# SCH.net
KiCad netlist of a schematic drawn in EasyEDA Pro
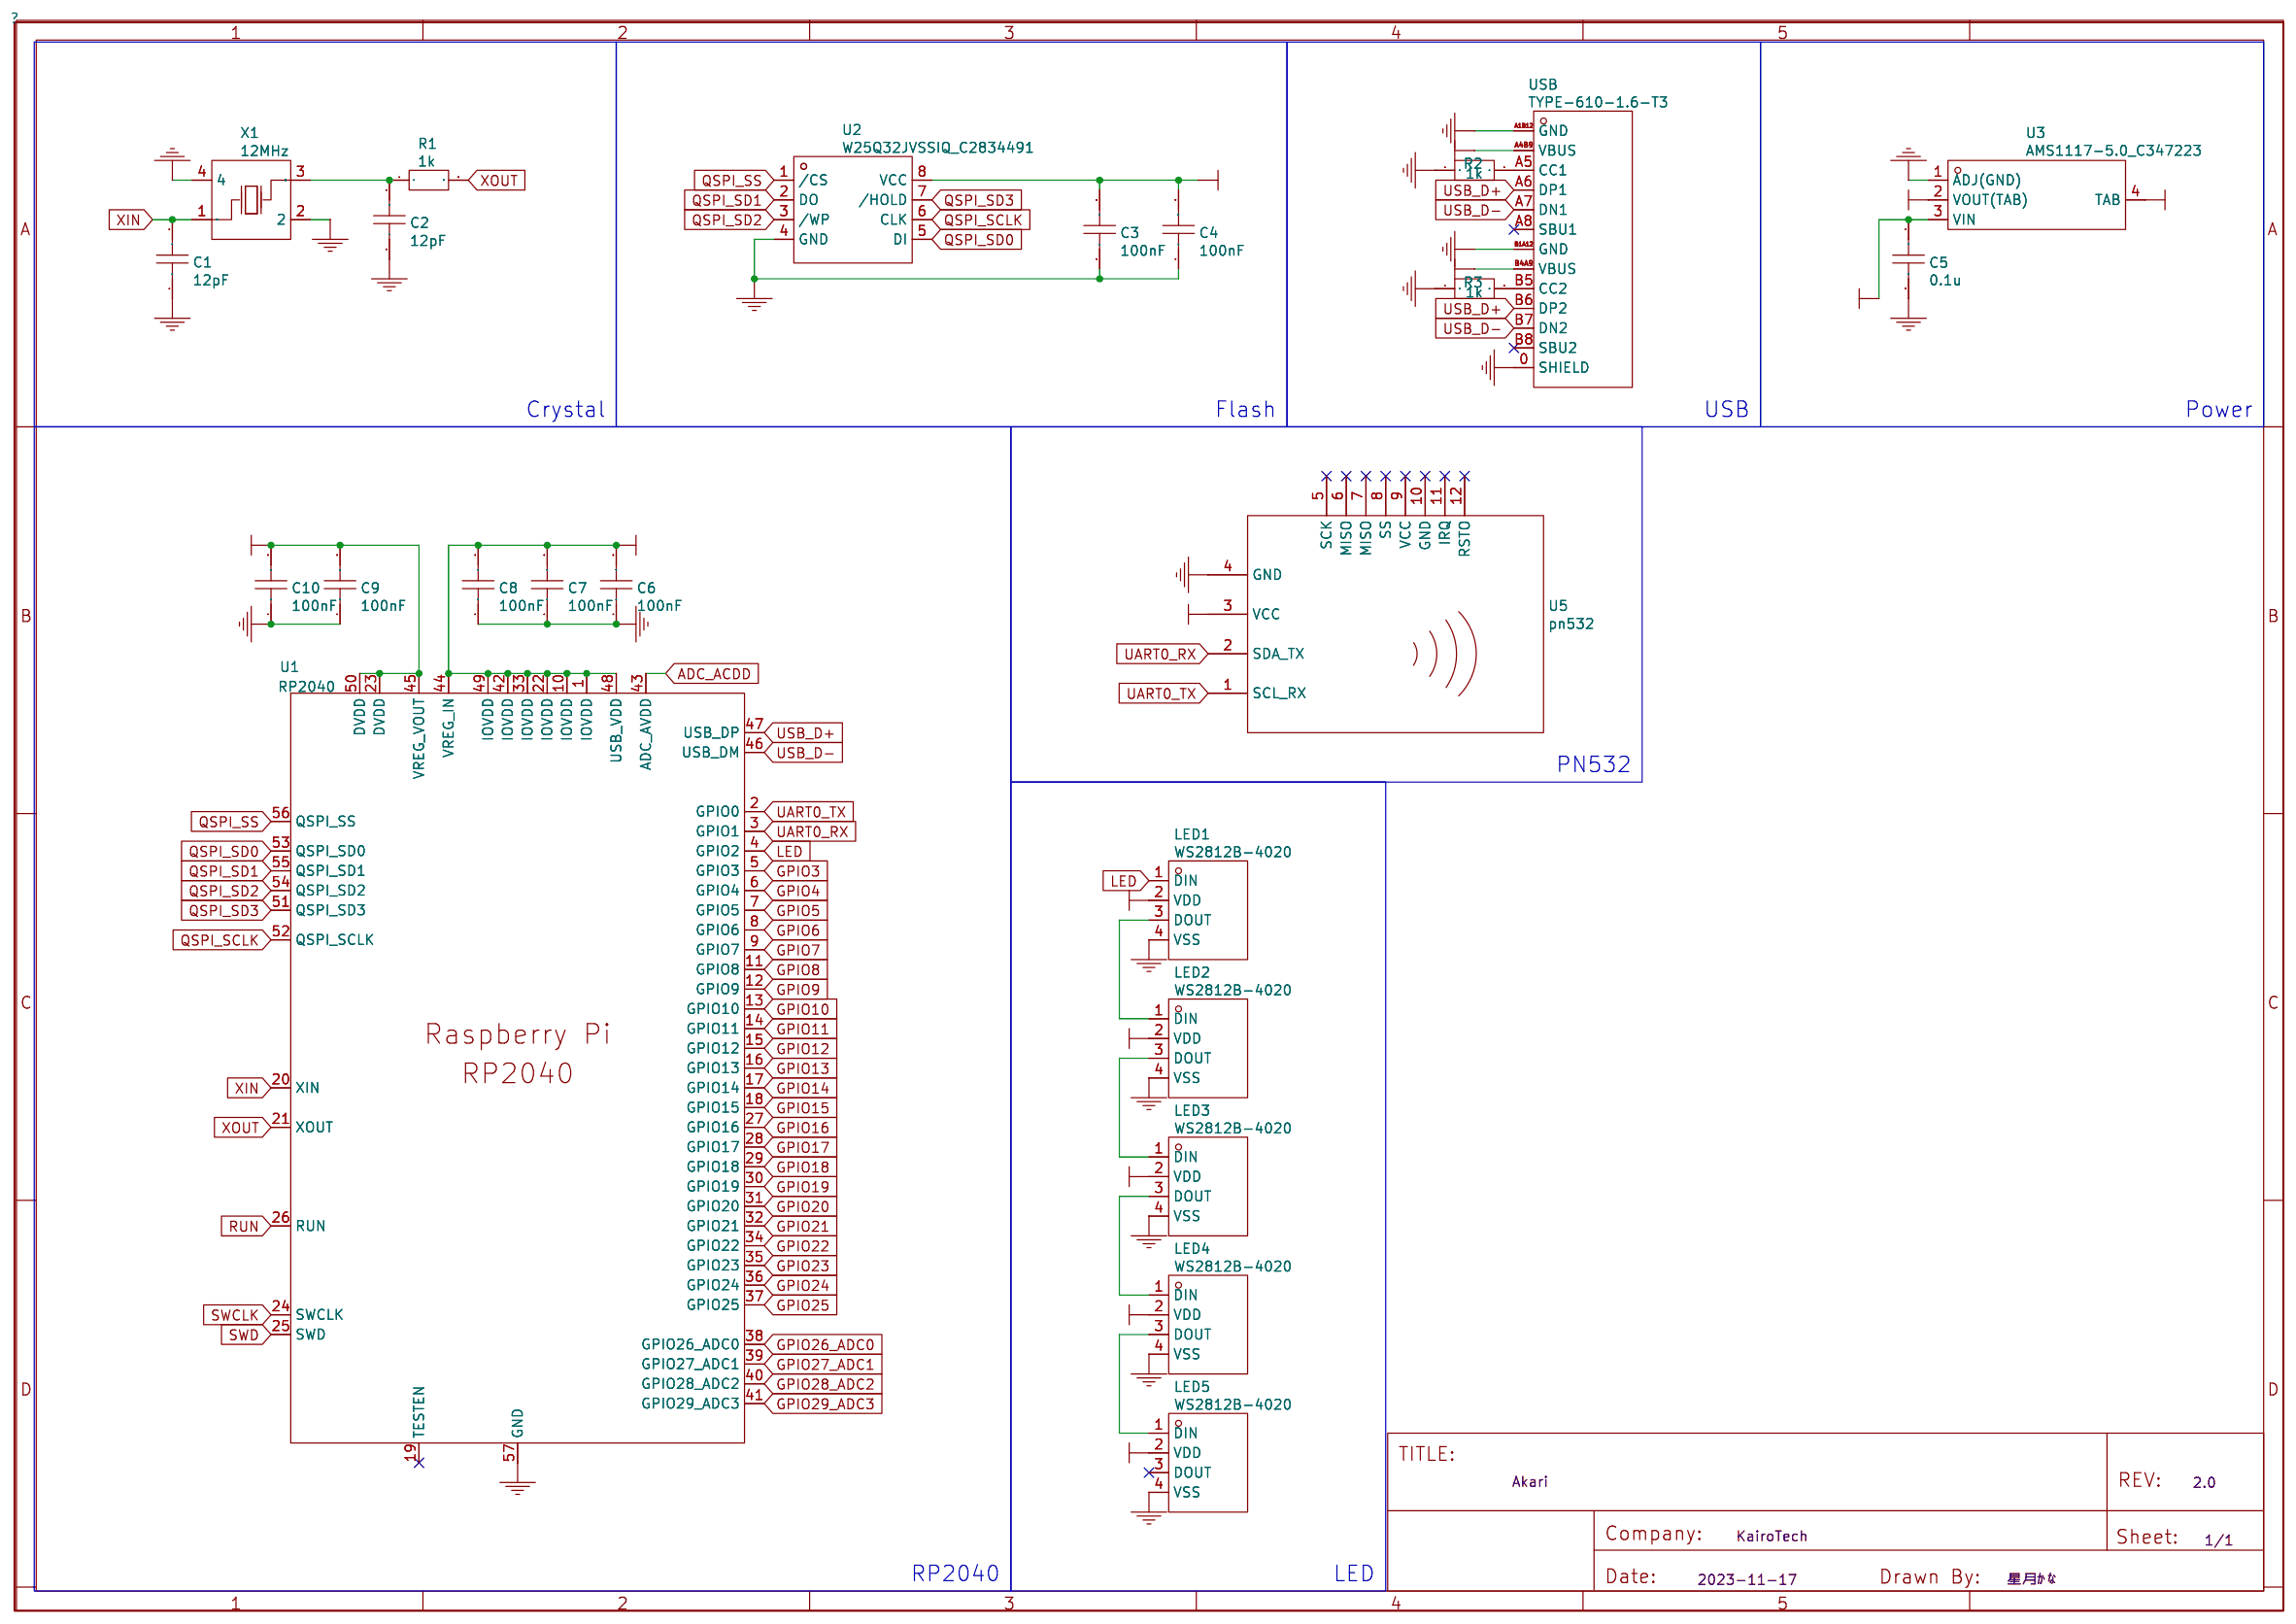
[diagram p0: schematic sheet]

(export (version "E")
  (design (tool "Eeschema 10.0.6"))
  (components
    (comp (ref "C1")
      (value "12pF")
      (footprint "easyedapro:C0603")
      (libsource (lib "easyedapro") (part "12pF"))
    )
    (comp (ref "C2")
      (value "12pF")
      (footprint "easyedapro:C0603")
      (libsource (lib "easyedapro") (part "12pF"))
    )
    (comp (ref "C3")
      (value "100nF")
      (footprint "easyedapro:C0603")
      (libsource (lib "easyedapro") (part "100nF"))
    )
    (comp (ref "C4")
      (value "100nF")
      (footprint "easyedapro:C0603")
      (libsource (lib "easyedapro") (part "100nF"))
    )
    (comp (ref "C5")
      (value "0.1u")
      (footprint "easyedapro:C0603")
      (libsource (lib "easyedapro") (part "0.1u"))
    )
    (comp (ref "C6")
      (value "100nF")
      (footprint "easyedapro:C0603")
      (libsource (lib "easyedapro") (part "100nF"))
    )
    (comp (ref "C7")
      (value "100nF")
      (footprint "easyedapro:C0603")
      (libsource (lib "easyedapro") (part "100nF"))
    )
    (comp (ref "C8")
      (value "100nF")
      (footprint "easyedapro:C0603")
      (libsource (lib "easyedapro") (part "100nF"))
    )
    (comp (ref "C9")
      (value "100nF")
      (footprint "easyedapro:C0603")
      (libsource (lib "easyedapro") (part "100nF"))
    )
    (comp (ref "C10")
      (value "100nF")
      (footprint "easyedapro:C0603")
      (libsource (lib "easyedapro") (part "100nF"))
    )
    (comp (ref "LED1")
      (value "WS2812B-4020")
      (footprint "easyedapro:LED-SMD_WS2812B-4020")
      (fields (field (name "Manufacturer") "worldsemi"))
      (libsource (lib "easyedapro") (part "WS2812B-4020"))
    )
    (comp (ref "LED2")
      (value "WS2812B-4020")
      (footprint "easyedapro:LED-SMD_WS2812B-4020")
      (fields (field (name "Manufacturer") "worldsemi"))
      (libsource (lib "easyedapro") (part "WS2812B-4020"))
    )
    (comp (ref "LED3")
      (value "WS2812B-4020")
      (footprint "easyedapro:LED-SMD_WS2812B-4020")
      (fields (field (name "Manufacturer") "worldsemi"))
      (libsource (lib "easyedapro") (part "WS2812B-4020"))
    )
    (comp (ref "LED4")
      (value "WS2812B-4020")
      (footprint "easyedapro:LED-SMD_WS2812B-4020")
      (fields (field (name "Manufacturer") "worldsemi"))
      (libsource (lib "easyedapro") (part "WS2812B-4020"))
    )
    (comp (ref "LED5")
      (value "WS2812B-4020")
      (footprint "easyedapro:LED-SMD_WS2812B-4020")
      (fields (field (name "Manufacturer") "worldsemi"))
      (libsource (lib "easyedapro") (part "WS2812B-4020"))
    )
    (comp (ref "R1") (value "1k") (footprint "easyedapro:R0603") (libsource (lib "easyedapro") (part "1k")))
    (comp (ref "R2") (value "1k") (footprint "easyedapro:R0603") (libsource (lib "easyedapro") (part "1k")))
    (comp (ref "R3") (value "1k") (footprint "easyedapro:R0603") (libsource (lib "easyedapro") (part "1k")))
    (comp (ref "U1")
      (value "RP2040")
      (footprint "easyedapro:LQFN-56_L7.0-W7.0-P0.4-EP")
      (fields (field (name "Manufacturer") "Raspberry Pi(树莓派)"))
      (libsource (lib "easyedapro") (part "RP2040"))
    )
    (comp (ref "U2")
      (value "W25Q32JVSSIQ_C2834491")
      (footprint "easyedapro:SOIC-8_L5.2-W5.2-P1.27-LS7.9-BL")
      (fields (field (name "Manufacturer Part") "W25Q32JVSSIQ") (field (name "Manufacturer") "WINBOND(华邦)"))
      (libsource (lib "easyedapro") (part "W25Q32JVSSIQ_C2834491"))
    )
    (comp (ref "U3")
      (value "AMS1117-5.0_C347223")
      (footprint "easyedapro:SOT-223_L6.7-W3.5-P2.30-BR")
      (fields (field (name "Manufacturer Part") "AMS1117-5.0") (field (name "Manufacturer") "UMW(广东友台半导体)"))
      (libsource (lib "easyedapro") (part "AMS1117-5.0_C347223"))
    )
    (comp (ref "U5")
      (value "pn532")
      (footprint "easyedapro:PN532")
      (libsource (lib "easyedapro") (part "pn532"))
    )
    (comp (ref "USB")
      (value "TYPE-610-1.6-T3")
      (footprint "easyedapro:USB-C-SMD_TYPE-C-16P-610-1.6-T3")
      (fields (field (name "Manufacturer") "Yuandi(元迪)"))
      (libsource (lib "easyedapro") (part "TYPE-610-1.6-T3"))
    )
    (comp (ref "X1")
      (value "12MHz")
      (footprint "easyedapro:CRYSTAL-SMD_4P-L2.5-W2.0-BL_XTAL12MHZ")
      (fields
        (field (name "Manufacturer Part") "ABM10AIG-12.000MHZ-4Z-T3")
        (field (name "Manufacturer") "ABRACON")
      )
      (libsource (lib "easyedapro") (part "12MHz"))
    )
  )
  (nets
    (net (code "1") (name "1V1") (class "Default")
      (node (ref "C10") (pin "2") (pinfunction "2_2") (pintype "unspecified"))
      (node (ref "C9") (pin "2") (pinfunction "2_2") (pintype "unspecified"))
      (node (ref "U1") (pin "23") (pinfunction "DVDD_23") (pintype "bidirectional"))
      (node (ref "U1") (pin "45") (pinfunction "VREG_VOUT_45") (pintype "bidirectional"))
      (node (ref "U1") (pin "50") (pinfunction "DVDD_50") (pintype "bidirectional"))
    )
    (net (code "2") (name "3V3") (class "Default")
      (node (ref "C3") (pin "2") (pinfunction "2_2") (pintype "unspecified"))
      (node (ref "C4") (pin "2") (pinfunction "2_2") (pintype "unspecified"))
      (node (ref "C6") (pin "2") (pinfunction "2_2") (pintype "unspecified"))
      (node (ref "C7") (pin "2") (pinfunction "2_2") (pintype "unspecified"))
      (node (ref "C8") (pin "2") (pinfunction "2_2") (pintype "unspecified"))
      (node (ref "U1") (pin "1") (pinfunction "IOVDD_1") (pintype "bidirectional"))
      (node (ref "U1") (pin "10") (pinfunction "IOVDD_10") (pintype "bidirectional"))
      (node (ref "U1") (pin "22") (pinfunction "IOVDD_22") (pintype "bidirectional"))
      (node (ref "U1") (pin "33") (pinfunction "IOVDD_33") (pintype "bidirectional"))
      (node (ref "U1") (pin "42") (pinfunction "IOVDD_42") (pintype "bidirectional"))
      (node (ref "U1") (pin "44") (pinfunction "VREG_IN_44") (pintype "bidirectional"))
      (node (ref "U1") (pin "48") (pinfunction "USB_VDD_48") (pintype "bidirectional"))
      (node (ref "U1") (pin "49") (pinfunction "IOVDD_49") (pintype "bidirectional"))
      (node (ref "U2") (pin "8") (pinfunction "VCC_8") (pintype "unspecified"))
      (node (ref "U3") (pin "2") (pinfunction "VOUT(TAB)_2") (pintype "unspecified"))
      (node (ref "U3") (pin "4") (pinfunction "TAB_4") (pintype "unspecified"))
    )
    (net (code "3") (name "ADC_ACDD") (class "Default")
      (node (ref "U1") (pin "43") (pinfunction "ADC_AVDD_43") (pintype "bidirectional"))
    )
    (net (code "4") (name "GND") (class "Default")
      (node (ref "C1") (pin "1") (pinfunction "1_1") (pintype "unspecified"))
      (node (ref "C10") (pin "1") (pinfunction "1_1") (pintype "unspecified"))
      (node (ref "C2") (pin "2") (pinfunction "2_2") (pintype "unspecified"))
      (node (ref "C3") (pin "1") (pinfunction "1_1") (pintype "unspecified"))
      (node (ref "C4") (pin "1") (pinfunction "1_1") (pintype "unspecified"))
      (node (ref "C5") (pin "2") (pinfunction "2_2") (pintype "unspecified"))
      (node (ref "C6") (pin "1") (pinfunction "1_1") (pintype "unspecified"))
      (node (ref "C7") (pin "1") (pinfunction "1_1") (pintype "unspecified"))
      (node (ref "C8") (pin "1") (pinfunction "1_1") (pintype "unspecified"))
      (node (ref "C9") (pin "1") (pinfunction "1_1") (pintype "unspecified"))
      (node (ref "LED1") (pin "4") (pinfunction "VSS_4") (pintype "unspecified"))
      (node (ref "LED2") (pin "4") (pinfunction "VSS_4") (pintype "unspecified"))
      (node (ref "LED3") (pin "4") (pinfunction "VSS_4") (pintype "unspecified"))
      (node (ref "LED4") (pin "4") (pinfunction "VSS_4") (pintype "unspecified"))
      (node (ref "LED5") (pin "4") (pinfunction "VSS_4") (pintype "unspecified"))
      (node (ref "R2") (pin "1") (pinfunction "1_1") (pintype "unspecified"))
      (node (ref "R3") (pin "1") (pinfunction "1_1") (pintype "unspecified"))
      (node (ref "U1") (pin "57") (pinfunction "GND_57") (pintype "bidirectional"))
      (node (ref "U2") (pin "4") (pinfunction "GND_4") (pintype "unspecified"))
      (node (ref "U3") (pin "1") (pinfunction "ADJ(GND)_1") (pintype "unspecified"))
      (node (ref "U5") (pin "4") (pinfunction "GND_4") (pintype "unspecified"))
      (node (ref "USB") (pin "0") (pinfunction "SHIELD_0") (pintype "unspecified"))
      (node (ref "USB") (pin "A1B12") (pinfunction "GND_A1B12") (pintype "unspecified"))
      (node (ref "USB") (pin "B1A12") (pinfunction "GND_B1A12") (pintype "unspecified"))
      (node (ref "X1") (pin "2") (pinfunction "2_2") (pintype "unspecified"))
      (node (ref "X1") (pin "4") (pinfunction "4_4") (pintype "unspecified"))
    )
    (net (code "5") (name "GPIO3") (class "Default")
      (node (ref "U1") (pin "5") (pinfunction "GPIO3_5") (pintype "bidirectional"))
    )
    (net (code "6") (name "GPIO4") (class "Default")
      (node (ref "U1") (pin "6") (pinfunction "GPIO4_6") (pintype "bidirectional"))
    )
    (net (code "7") (name "GPIO5") (class "Default")
      (node (ref "U1") (pin "7") (pinfunction "GPIO5_7") (pintype "bidirectional"))
    )
    (net (code "8") (name "GPIO6") (class "Default")
      (node (ref "U1") (pin "8") (pinfunction "GPIO6_8") (pintype "bidirectional"))
    )
    (net (code "9") (name "GPIO7") (class "Default")
      (node (ref "U1") (pin "9") (pinfunction "GPIO7_9") (pintype "bidirectional"))
    )
    (net (code "10") (name "GPIO8") (class "Default")
      (node (ref "U1") (pin "11") (pinfunction "GPIO8_11") (pintype "bidirectional"))
    )
    (net (code "11") (name "GPIO9") (class "Default")
      (node (ref "U1") (pin "12") (pinfunction "GPIO9_12") (pintype "bidirectional"))
    )
    (net (code "12") (name "GPIO10") (class "Default")
      (node (ref "U1") (pin "13") (pinfunction "GPIO10_13") (pintype "bidirectional"))
    )
    (net (code "13") (name "GPIO11") (class "Default")
      (node (ref "U1") (pin "14") (pinfunction "GPIO11_14") (pintype "bidirectional"))
    )
    (net (code "14") (name "GPIO12") (class "Default")
      (node (ref "U1") (pin "15") (pinfunction "GPIO12_15") (pintype "bidirectional"))
    )
    (net (code "15") (name "GPIO13") (class "Default")
      (node (ref "U1") (pin "16") (pinfunction "GPIO13_16") (pintype "bidirectional"))
    )
    (net (code "16") (name "GPIO14") (class "Default")
      (node (ref "U1") (pin "17") (pinfunction "GPIO14_17") (pintype "bidirectional"))
    )
    (net (code "17") (name "GPIO15") (class "Default")
      (node (ref "U1") (pin "18") (pinfunction "GPIO15_18") (pintype "bidirectional"))
    )
    (net (code "18") (name "GPIO16") (class "Default")
      (node (ref "U1") (pin "27") (pinfunction "GPIO16_27") (pintype "bidirectional"))
    )
    (net (code "19") (name "GPIO17") (class "Default")
      (node (ref "U1") (pin "28") (pinfunction "GPIO17_28") (pintype "bidirectional"))
    )
    (net (code "20") (name "GPIO18") (class "Default")
      (node (ref "U1") (pin "29") (pinfunction "GPIO18_29") (pintype "bidirectional"))
    )
    (net (code "21") (name "GPIO19") (class "Default")
      (node (ref "U1") (pin "30") (pinfunction "GPIO19_30") (pintype "bidirectional"))
    )
    (net (code "22") (name "GPIO20") (class "Default")
      (node (ref "U1") (pin "31") (pinfunction "GPIO20_31") (pintype "bidirectional"))
    )
    (net (code "23") (name "GPIO21") (class "Default")
      (node (ref "U1") (pin "32") (pinfunction "GPIO21_32") (pintype "bidirectional"))
    )
    (net (code "24") (name "GPIO22") (class "Default")
      (node (ref "U1") (pin "34") (pinfunction "GPIO22_34") (pintype "bidirectional"))
    )
    (net (code "25") (name "GPIO23") (class "Default")
      (node (ref "U1") (pin "35") (pinfunction "GPIO23_35") (pintype "bidirectional"))
    )
    (net (code "26") (name "GPIO24") (class "Default")
      (node (ref "U1") (pin "36") (pinfunction "GPIO24_36") (pintype "bidirectional"))
    )
    (net (code "27") (name "GPIO25") (class "Default")
      (node (ref "U1") (pin "37") (pinfunction "GPIO25_37") (pintype "bidirectional"))
    )
    (net (code "28") (name "GPIO26_ADC0") (class "Default")
      (node (ref "U1") (pin "38") (pinfunction "GPIO26_ADC0_38") (pintype "bidirectional"))
    )
    (net (code "29") (name "GPIO27_ADC1") (class "Default")
      (node (ref "U1") (pin "39") (pinfunction "GPIO27_ADC1_39") (pintype "bidirectional"))
    )
    (net (code "30") (name "GPIO28_ADC2") (class "Default")
      (node (ref "U1") (pin "40") (pinfunction "GPIO28_ADC2_40") (pintype "bidirectional"))
    )
    (net (code "31") (name "GPIO29_ADC3") (class "Default")
      (node (ref "U1") (pin "41") (pinfunction "GPIO29_ADC3_41") (pintype "bidirectional"))
    )
    (net (code "32") (name "LED") (class "Default")
      (node (ref "LED1") (pin "1") (pinfunction "DIN_1") (pintype "unspecified"))
      (node (ref "U1") (pin "4") (pinfunction "GPIO2_4") (pintype "bidirectional"))
    )
    (net (code "33") (name "Net-(LED1-DOUT)") (class "Default")
      (node (ref "LED1") (pin "3") (pinfunction "DOUT_3") (pintype "unspecified"))
      (node (ref "LED2") (pin "1") (pinfunction "DIN_1") (pintype "unspecified"))
    )
    (net (code "34") (name "Net-(LED2-DOUT)") (class "Default")
      (node (ref "LED2") (pin "3") (pinfunction "DOUT_3") (pintype "unspecified"))
      (node (ref "LED3") (pin "1") (pinfunction "DIN_1") (pintype "unspecified"))
    )
    (net (code "35") (name "Net-(LED3-DOUT)") (class "Default")
      (node (ref "LED3") (pin "3") (pinfunction "DOUT_3") (pintype "unspecified"))
      (node (ref "LED4") (pin "1") (pinfunction "DIN_1") (pintype "unspecified"))
    )
    (net (code "36") (name "Net-(LED4-DOUT)") (class "Default")
      (node (ref "LED4") (pin "3") (pinfunction "DOUT_3") (pintype "unspecified"))
      (node (ref "LED5") (pin "1") (pinfunction "DIN_1") (pintype "unspecified"))
    )
    (net (code "37") (name "Net-(USB-CC1)") (class "Default")
      (node (ref "R2") (pin "2") (pinfunction "2_2") (pintype "unspecified"))
      (node (ref "USB") (pin "A5") (pinfunction "CC1_A5") (pintype "unspecified"))
    )
    (net (code "38") (name "Net-(USB-CC2)") (class "Default")
      (node (ref "R3") (pin "2") (pinfunction "2_2") (pintype "unspecified"))
      (node (ref "USB") (pin "B5") (pinfunction "CC2_B5") (pintype "unspecified"))
    )
    (net (code "39") (name "Net-(X1-OSC2)") (class "Default")
      (node (ref "C2") (pin "1") (pinfunction "1_1") (pintype "unspecified"))
      (node (ref "R1") (pin "1") (pinfunction "1_1") (pintype "unspecified"))
      (node (ref "X1") (pin "3") (pinfunction "OSC2_3") (pintype "unspecified"))
    )
    (net (code "40") (name "QSPI_SCLK") (class "Default")
      (node (ref "U1") (pin "52") (pinfunction "QSPI_SCLK_52") (pintype "output"))
      (node (ref "U2") (pin "6") (pinfunction "CLK_6") (pintype "unspecified"))
    )
    (net (code "41") (name "QSPI_SD0") (class "Default")
      (node (ref "U1") (pin "53") (pinfunction "QSPI_SD0_53") (pintype "bidirectional"))
      (node (ref "U2") (pin "5") (pinfunction "DI_5") (pintype "unspecified"))
    )
    (net (code "42") (name "QSPI_SD1") (class "Default")
      (node (ref "U1") (pin "55") (pinfunction "QSPI_SD1_55") (pintype "bidirectional"))
      (node (ref "U2") (pin "2") (pinfunction "DO_2") (pintype "unspecified"))
    )
    (net (code "43") (name "QSPI_SD2") (class "Default")
      (node (ref "U1") (pin "54") (pinfunction "QSPI_SD2_54") (pintype "bidirectional"))
      (node (ref "U2") (pin "3") (pinfunction "/WP_3") (pintype "unspecified"))
    )
    (net (code "44") (name "QSPI_SD3") (class "Default")
      (node (ref "U1") (pin "51") (pinfunction "QSPI_SD3_51") (pintype "bidirectional"))
      (node (ref "U2") (pin "7") (pinfunction "/HOLD_7") (pintype "unspecified"))
    )
    (net (code "45") (name "QSPI_SS") (class "Default")
      (node (ref "U1") (pin "56") (pinfunction "QSPI_SS_56") (pintype "bidirectional"))
      (node (ref "U2") (pin "1") (pinfunction "/CS_1") (pintype "unspecified"))
    )
    (net (code "46") (name "RUN") (class "Default")
      (node (ref "U1") (pin "26") (pinfunction "RUN_26") (pintype "input"))
    )
    (net (code "47") (name "SWCLK") (class "Default")
      (node (ref "U1") (pin "24") (pinfunction "SWCLK_24") (pintype "output"))
    )
    (net (code "48") (name "SWD") (class "Default")
      (node (ref "U1") (pin "25") (pinfunction "SWD_25") (pintype "bidirectional"))
    )
    (net (code "49") (name "UART0_RX") (class "Default")
      (node (ref "U1") (pin "3") (pinfunction "GPIO1_3") (pintype "bidirectional"))
      (node (ref "U5") (pin "2") (pinfunction "SDA_TX_2") (pintype "unspecified"))
    )
    (net (code "50") (name "UART0_TX") (class "Default")
      (node (ref "U1") (pin "2") (pinfunction "GPIO0_2") (pintype "bidirectional"))
      (node (ref "U5") (pin "1") (pinfunction "SCL_RX_1") (pintype "unspecified"))
    )
    (net (code "51") (name "USB_D+") (class "Default")
      (node (ref "U1") (pin "47") (pinfunction "USB_DP_47") (pintype "bidirectional"))
      (node (ref "USB") (pin "A6") (pinfunction "DP1_A6") (pintype "unspecified"))
      (node (ref "USB") (pin "B6") (pinfunction "DP2_B6") (pintype "unspecified"))
    )
    (net (code "52") (name "USB_D-") (class "Default")
      (node (ref "U1") (pin "46") (pinfunction "USB_DM_46") (pintype "bidirectional"))
      (node (ref "USB") (pin "A7") (pinfunction "DN1_A7") (pintype "unspecified"))
      (node (ref "USB") (pin "B7") (pinfunction "DN2_B7") (pintype "unspecified"))
    )
    (net (code "53") (name "VCC") (class "Default")
      (node (ref "C5") (pin "1") (pinfunction "1_1") (pintype "unspecified"))
      (node (ref "LED1") (pin "2") (pinfunction "VDD_2") (pintype "unspecified"))
      (node (ref "LED2") (pin "2") (pinfunction "VDD_2") (pintype "unspecified"))
      (node (ref "LED3") (pin "2") (pinfunction "VDD_2") (pintype "unspecified"))
      (node (ref "LED4") (pin "2") (pinfunction "VDD_2") (pintype "unspecified"))
      (node (ref "LED5") (pin "2") (pinfunction "VDD_2") (pintype "unspecified"))
      (node (ref "U3") (pin "3") (pinfunction "VIN_3") (pintype "unspecified"))
      (node (ref "U5") (pin "3") (pinfunction "VCC_3") (pintype "unspecified"))
      (node (ref "USB") (pin "A4B9") (pinfunction "VBUS_A4B9") (pintype "unspecified"))
      (node (ref "USB") (pin "B4A9") (pinfunction "VBUS_B4A9") (pintype "unspecified"))
    )
    (net (code "54") (name "XIN") (class "Default")
      (node (ref "C1") (pin "2") (pinfunction "2_2") (pintype "unspecified"))
      (node (ref "U1") (pin "20") (pinfunction "XIN_20") (pintype "input"))
      (node (ref "X1") (pin "1") (pinfunction "OSC1_1") (pintype "unspecified"))
    )
    (net (code "55") (name "XOUT") (class "Default")
      (node (ref "R1") (pin "2") (pinfunction "2_2") (pintype "unspecified"))
      (node (ref "U1") (pin "21") (pinfunction "XOUT_21") (pintype "unspecified"))
    )
    (net (code "56") (name "unconnected-(LED5-DOUT-Pad3)") (class "Default")
      (node (ref "LED5") (pin "3") (pinfunction "DOUT_3") (pintype "unspecified+no_connect"))
    )
    (net (code "57") (name "unconnected-(U1-TESTEN-Pad19)") (class "Default")
      (node (ref "U1") (pin "19") (pinfunction "TESTEN_19") (pintype "unspecified+no_connect"))
    )
    (net (code "58") (name "unconnected-(U5-GND-Pad10)") (class "Default")
      (node (ref "U5") (pin "10") (pinfunction "GND_10") (pintype "unspecified+no_connect"))
    )
    (net (code "59") (name "unconnected-(U5-IRQ-Pad11)") (class "Default")
      (node (ref "U5") (pin "11") (pinfunction "IRQ_11") (pintype "unspecified+no_connect"))
    )
    (net (code "60") (name "unconnected-(U5-MISO-Pad6)") (class "Default")
      (node (ref "U5") (pin "6") (pinfunction "MISO_6") (pintype "unspecified+no_connect"))
    )
    (net (code "61") (name "unconnected-(U5-MISO-Pad7)") (class "Default")
      (node (ref "U5") (pin "7") (pinfunction "MISO_7") (pintype "unspecified+no_connect"))
    )
    (net (code "62") (name "unconnected-(U5-RSTO-Pad12)") (class "Default")
      (node (ref "U5") (pin "12") (pinfunction "RSTO_12") (pintype "unspecified+no_connect"))
    )
    (net (code "63") (name "unconnected-(U5-SCK-Pad5)") (class "Default")
      (node (ref "U5") (pin "5") (pinfunction "SCK_5") (pintype "unspecified+no_connect"))
    )
    (net (code "64") (name "unconnected-(U5-SS-Pad8)") (class "Default")
      (node (ref "U5") (pin "8") (pinfunction "SS_8") (pintype "unspecified+no_connect"))
    )
    (net (code "65") (name "unconnected-(U5-VCC-Pad9)") (class "Default")
      (node (ref "U5") (pin "9") (pinfunction "VCC_9") (pintype "unspecified+no_connect"))
    )
    (net (code "66") (name "unconnected-(USB-SBU1-PadA8)") (class "Default")
      (node (ref "USB") (pin "A8") (pinfunction "SBU1_A8") (pintype "unspecified+no_connect"))
    )
    (net (code "67") (name "unconnected-(USB-SBU2-PadB8)") (class "Default")
      (node (ref "USB") (pin "B8") (pinfunction "SBU2_B8") (pintype "unspecified+no_connect"))
    )
  )
)
